# SCH_WIRING-SOLENOID_2026-09-01.net
KiCad netlist of a schematic drawn in EasyEDA
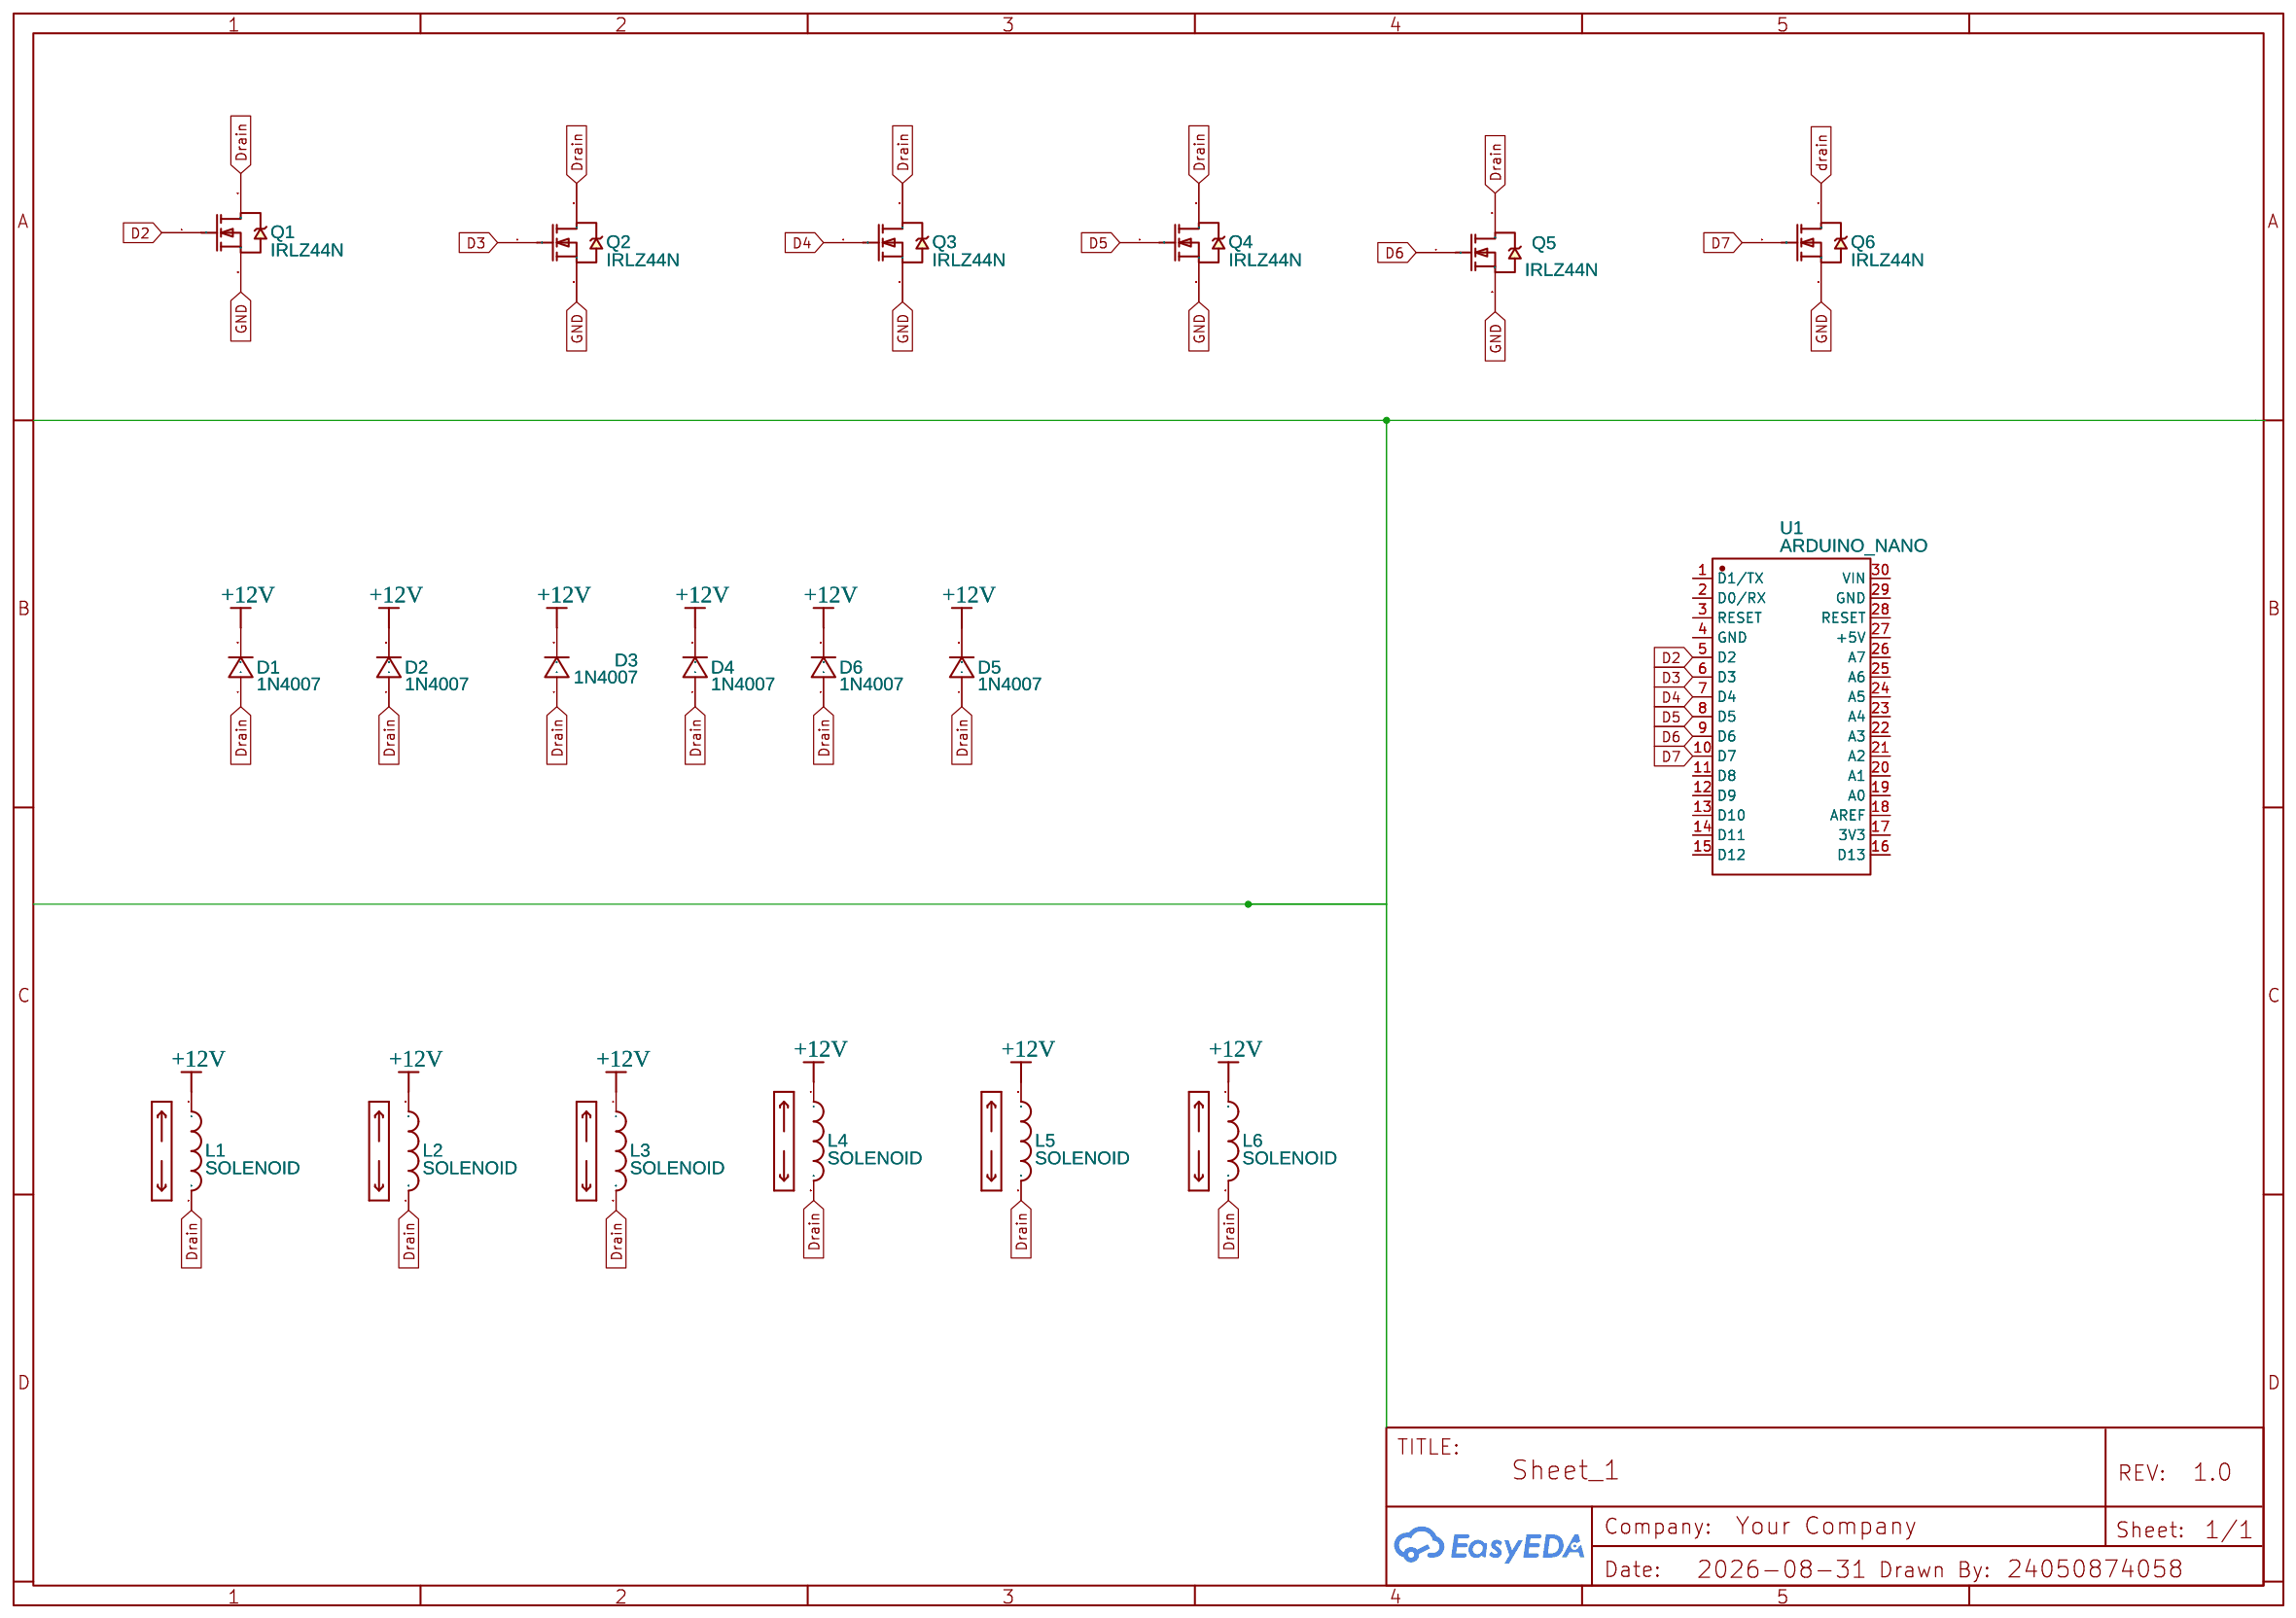
[diagram p0: schematic sheet]

(export (version "E")
  (design (tool "Eeschema 10.0.6"))
  (components
    (comp (ref "D1")
      (value "1N4007")
      (fields (field (name "Manufacturer") "Changzhou Starsea Elec"))
      (libsource (lib "") (part "1N4007"))
    )
    (comp (ref "D2")
      (value "1N4007")
      (fields (field (name "Manufacturer") "Changzhou Starsea Elec"))
      (libsource (lib "") (part "1N4007"))
    )
    (comp (ref "D3")
      (value "1N4007")
      (fields (field (name "Manufacturer") "Changzhou Starsea Elec"))
      (libsource (lib "") (part "1N4007_1"))
    )
    (comp (ref "D4")
      (value "1N4007")
      (fields (field (name "Manufacturer") "Changzhou Starsea Elec"))
      (libsource (lib "") (part "1N4007"))
    )
    (comp (ref "D5")
      (value "1N4007")
      (fields (field (name "Manufacturer") "Changzhou Starsea Elec"))
      (libsource (lib "") (part "1N4007"))
    )
    (comp (ref "D6")
      (value "1N4007")
      (fields (field (name "Manufacturer") "Changzhou Starsea Elec"))
      (libsource (lib "") (part "1N4007"))
    )
    (comp (ref "L1") (value "SOLENOID") (libsource (lib "") (part "SOLENOID")))
    (comp (ref "L2") (value "SOLENOID") (libsource (lib "") (part "SOLENOID")))
    (comp (ref "L3") (value "SOLENOID") (libsource (lib "") (part "SOLENOID")))
    (comp (ref "L4") (value "SOLENOID") (libsource (lib "") (part "SOLENOID")))
    (comp (ref "L5") (value "SOLENOID") (libsource (lib "") (part "SOLENOID")))
    (comp (ref "L6") (value "SOLENOID") (libsource (lib "") (part "SOLENOID")))
    (comp (ref "Q1") (value "IRLZ44N") (libsource (lib "") (part "IRLZ44N")))
    (comp (ref "Q2") (value "IRLZ44N") (libsource (lib "") (part "IRLZ44N")))
    (comp (ref "Q3") (value "IRLZ44N") (libsource (lib "") (part "IRLZ44N")))
    (comp (ref "Q4") (value "IRLZ44N") (libsource (lib "") (part "IRLZ44N")))
    (comp (ref "Q5") (value "IRLZ44N") (libsource (lib "") (part "IRLZ44N")))
    (comp (ref "Q6") (value "IRLZ44N") (libsource (lib "") (part "IRLZ44N")))
    (comp (ref "U1") (value "ARDUINO_NANO") (libsource (lib "") (part "ARDUINO_NANO")))
  )
  (nets
    (net (code "1") (name "+12V") (class "Default")
      (node (ref "D1") (pin "2") (pinfunction "2_2") (pintype "unspecified"))
      (node (ref "D2") (pin "2") (pinfunction "2_2") (pintype "unspecified"))
      (node (ref "D3") (pin "2") (pinfunction "2_2") (pintype "unspecified"))
      (node (ref "D4") (pin "2") (pinfunction "2_2") (pintype "unspecified"))
      (node (ref "D5") (pin "2") (pinfunction "2_2") (pintype "unspecified"))
      (node (ref "D6") (pin "2") (pinfunction "2_2") (pintype "unspecified"))
      (node (ref "L1") (pin "1") (pinfunction "1_1") (pintype "unspecified"))
      (node (ref "L2") (pin "1") (pinfunction "1_1") (pintype "unspecified"))
      (node (ref "L3") (pin "1") (pinfunction "1_1") (pintype "unspecified"))
      (node (ref "L4") (pin "1") (pinfunction "1_1") (pintype "unspecified"))
      (node (ref "L5") (pin "1") (pinfunction "1_1") (pintype "unspecified"))
      (node (ref "L6") (pin "1") (pinfunction "1_1") (pintype "unspecified"))
    )
    (net (code "2") (name "D2") (class "Default")
      (node (ref "Q1") (pin "1") (pinfunction "G_1") (pintype "unspecified"))
      (node (ref "U1") (pin "5") (pinfunction "D2_5") (pintype "unspecified"))
    )
    (net (code "3") (name "D3") (class "Default")
      (node (ref "Q2") (pin "1") (pinfunction "G_1") (pintype "unspecified"))
      (node (ref "U1") (pin "6") (pinfunction "D3_6") (pintype "unspecified"))
    )
    (net (code "4") (name "D4") (class "Default")
      (node (ref "Q3") (pin "1") (pinfunction "G_1") (pintype "unspecified"))
      (node (ref "U1") (pin "7") (pinfunction "D4_7") (pintype "unspecified"))
    )
    (net (code "5") (name "D5") (class "Default")
      (node (ref "Q4") (pin "1") (pinfunction "G_1") (pintype "unspecified"))
      (node (ref "U1") (pin "8") (pinfunction "D5_8") (pintype "unspecified"))
    )
    (net (code "6") (name "D6") (class "Default")
      (node (ref "Q5") (pin "1") (pinfunction "G_1") (pintype "unspecified"))
      (node (ref "U1") (pin "9") (pinfunction "D6_9") (pintype "unspecified"))
    )
    (net (code "7") (name "D7") (class "Default")
      (node (ref "Q6") (pin "1") (pinfunction "G_1") (pintype "unspecified"))
      (node (ref "U1") (pin "10") (pinfunction "D7_10") (pintype "unspecified"))
    )
    (net (code "8") (name "Drain") (class "Default")
      (node (ref "D1") (pin "1") (pinfunction "1_1") (pintype "unspecified"))
      (node (ref "D2") (pin "1") (pinfunction "1_1") (pintype "unspecified"))
      (node (ref "D3") (pin "1") (pinfunction "1_1") (pintype "unspecified"))
      (node (ref "D4") (pin "1") (pinfunction "1_1") (pintype "unspecified"))
      (node (ref "D5") (pin "1") (pinfunction "1_1") (pintype "unspecified"))
      (node (ref "D6") (pin "1") (pinfunction "1_1") (pintype "unspecified"))
      (node (ref "L1") (pin "2") (pinfunction "2_2") (pintype "unspecified"))
      (node (ref "L2") (pin "2") (pinfunction "2_2") (pintype "unspecified"))
      (node (ref "L3") (pin "2") (pinfunction "2_2") (pintype "unspecified"))
      (node (ref "L4") (pin "2") (pinfunction "2_2") (pintype "unspecified"))
      (node (ref "L5") (pin "2") (pinfunction "2_2") (pintype "unspecified"))
      (node (ref "L6") (pin "2") (pinfunction "2_2") (pintype "unspecified"))
      (node (ref "Q1") (pin "2") (pinfunction "D_2") (pintype "unspecified"))
      (node (ref "Q2") (pin "2") (pinfunction "D_2") (pintype "unspecified"))
      (node (ref "Q3") (pin "2") (pinfunction "D_2") (pintype "unspecified"))
      (node (ref "Q4") (pin "2") (pinfunction "D_2") (pintype "unspecified"))
      (node (ref "Q5") (pin "2") (pinfunction "D_2") (pintype "unspecified"))
    )
    (net (code "9") (name "GND") (class "Default")
      (node (ref "Q1") (pin "3") (pinfunction "S_3") (pintype "unspecified"))
      (node (ref "Q2") (pin "3") (pinfunction "S_3") (pintype "unspecified"))
      (node (ref "Q3") (pin "3") (pinfunction "S_3") (pintype "unspecified"))
      (node (ref "Q4") (pin "3") (pinfunction "S_3") (pintype "unspecified"))
      (node (ref "Q5") (pin "3") (pinfunction "S_3") (pintype "unspecified"))
      (node (ref "Q6") (pin "3") (pinfunction "S_3") (pintype "unspecified"))
    )
    (net (code "10") (name "drain") (class "Default")
      (node (ref "Q6") (pin "2") (pinfunction "D_2") (pintype "unspecified"))
    )
    (net (code "11") (name "unconnected-(U1-+5V-Pad27)") (class "Default")
      (node (ref "U1") (pin "27") (pinfunction "+5V_27") (pintype "unspecified"))
    )
    (net (code "12") (name "unconnected-(U1-3V3-Pad17)") (class "Default")
      (node (ref "U1") (pin "17") (pinfunction "3V3_17") (pintype "unspecified"))
    )
    (net (code "13") (name "unconnected-(U1-A0-Pad19)") (class "Default")
      (node (ref "U1") (pin "19") (pinfunction "A0_19") (pintype "unspecified"))
    )
    (net (code "14") (name "unconnected-(U1-A1-Pad20)") (class "Default")
      (node (ref "U1") (pin "20") (pinfunction "A1_20") (pintype "unspecified"))
    )
    (net (code "15") (name "unconnected-(U1-A2-Pad21)") (class "Default")
      (node (ref "U1") (pin "21") (pinfunction "A2_21") (pintype "unspecified"))
    )
    (net (code "16") (name "unconnected-(U1-A3-Pad22)") (class "Default")
      (node (ref "U1") (pin "22") (pinfunction "A3_22") (pintype "unspecified"))
    )
    (net (code "17") (name "unconnected-(U1-A4-Pad23)") (class "Default")
      (node (ref "U1") (pin "23") (pinfunction "A4_23") (pintype "unspecified"))
    )
    (net (code "18") (name "unconnected-(U1-A5-Pad24)") (class "Default")
      (node (ref "U1") (pin "24") (pinfunction "A5_24") (pintype "unspecified"))
    )
    (net (code "19") (name "unconnected-(U1-A6-Pad25)") (class "Default")
      (node (ref "U1") (pin "25") (pinfunction "A6_25") (pintype "unspecified"))
    )
    (net (code "20") (name "unconnected-(U1-A7-Pad26)") (class "Default")
      (node (ref "U1") (pin "26") (pinfunction "A7_26") (pintype "unspecified"))
    )
    (net (code "21") (name "unconnected-(U1-AREF-Pad18)") (class "Default")
      (node (ref "U1") (pin "18") (pinfunction "AREF_18") (pintype "unspecified"))
    )
    (net (code "22") (name "unconnected-(U1-D0{slash}RX-Pad2)") (class "Default")
      (node (ref "U1") (pin "2") (pinfunction "D0/RX_2") (pintype "unspecified"))
    )
    (net (code "23") (name "unconnected-(U1-D1{slash}TX-Pad1)") (class "Default")
      (node (ref "U1") (pin "1") (pinfunction "D1/TX_1") (pintype "unspecified"))
    )
    (net (code "24") (name "unconnected-(U1-D8-Pad11)") (class "Default")
      (node (ref "U1") (pin "11") (pinfunction "D8_11") (pintype "unspecified"))
    )
    (net (code "25") (name "unconnected-(U1-D9-Pad12)") (class "Default")
      (node (ref "U1") (pin "12") (pinfunction "D9_12") (pintype "unspecified"))
    )
    (net (code "26") (name "unconnected-(U1-D10-Pad13)") (class "Default")
      (node (ref "U1") (pin "13") (pinfunction "D10_13") (pintype "unspecified"))
    )
    (net (code "27") (name "unconnected-(U1-D11-Pad14)") (class "Default")
      (node (ref "U1") (pin "14") (pinfunction "D11_14") (pintype "unspecified"))
    )
    (net (code "28") (name "unconnected-(U1-D12-Pad15)") (class "Default")
      (node (ref "U1") (pin "15") (pinfunction "D12_15") (pintype "unspecified"))
    )
    (net (code "29") (name "unconnected-(U1-D13-Pad16)") (class "Default")
      (node (ref "U1") (pin "16") (pinfunction "D13_16") (pintype "unspecified"))
    )
    (net (code "30") (name "unconnected-(U1-GND-Pad4)") (class "Default")
      (node (ref "U1") (pin "4") (pinfunction "GND_4") (pintype "unspecified"))
    )
    (net (code "31") (name "unconnected-(U1-GND-Pad29)") (class "Default")
      (node (ref "U1") (pin "29") (pinfunction "GND_29") (pintype "unspecified"))
    )
    (net (code "32") (name "unconnected-(U1-RESET-Pad3)") (class "Default")
      (node (ref "U1") (pin "3") (pinfunction "RESET_3") (pintype "unspecified"))
    )
    (net (code "33") (name "unconnected-(U1-RESET-Pad28)") (class "Default")
      (node (ref "U1") (pin "28") (pinfunction "RESET_28") (pintype "unspecified"))
    )
    (net (code "34") (name "unconnected-(U1-VIN-Pad30)") (class "Default")
      (node (ref "U1") (pin "30") (pinfunction "VIN_30") (pintype "unspecified"))
    )
  )
)
